# SpdReaderWriterSchematic.net
KiCad netlist of a schematic drawn in EAGLE
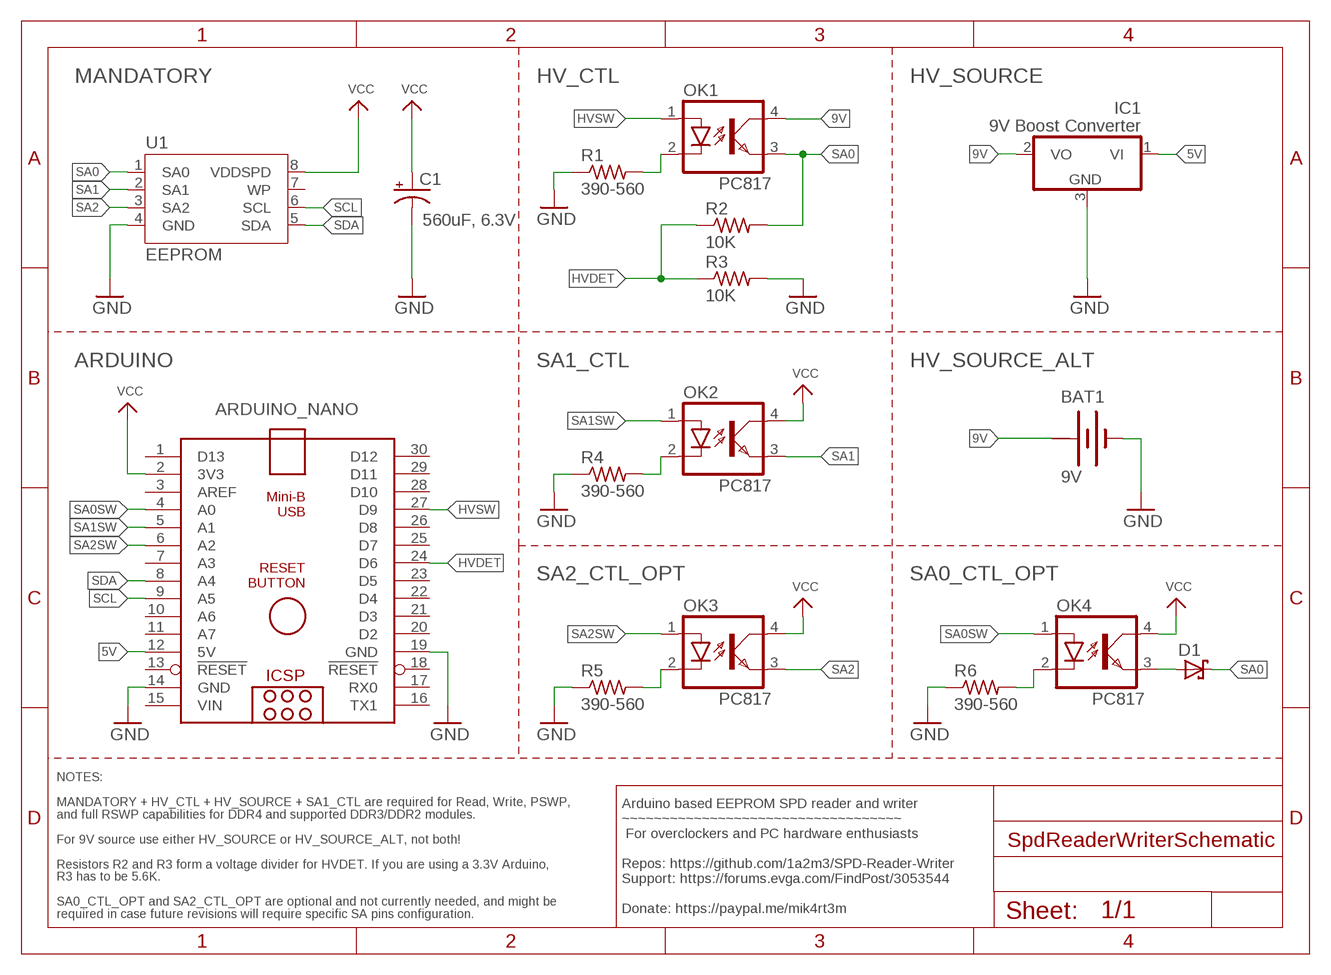
[diagram p0: schematic, sheet 1]

(export (version "E")
  (design (tool "Eeschema 10.0.6"))
  (components
    (comp (ref "ARDUINO_NANO")
      (value "ARDUINO_NANO")
      (footprint "eagle-import:ARDUINO_NANO")
      (libsource (lib "eagle-import") (part "ARDUINO_NANO"))
    )
    (comp (ref "BAT1")
      (value "9V")
      (footprint "eagle-import:BATTERY")
      (libsource (lib "eagle-import") (part "BATTERY"))
    )
    (comp (ref "C1")
      (value "560uF, 6.3V")
      (footprint "eagle-import:E5-8,5")
      (libsource (lib "eagle-import") (part "CPOL-USE5-8.5"))
    )
    (comp (ref "D1")
      (value "SCHOTTKY-DIODEDO35-7")
      (footprint "eagle-import:DO35-7")
      (libsource (lib "eagle-import") (part "SCHOTTKY-DIODEDO35-7"))
    )
    (comp (ref "IC1")
      (value "9V Boost Converter")
      (footprint "eagle-import:TO39")
      (libsource (lib "eagle-import") (part "78H24"))
    )
    (comp (ref "OK1")
      (value "PC817")
      (footprint "eagle-import:DIL04")
      (libsource (lib "eagle-import") (part "LTV816"))
    )
    (comp (ref "OK2")
      (value "PC817")
      (footprint "eagle-import:DIL04")
      (libsource (lib "eagle-import") (part "LTV816"))
    )
    (comp (ref "OK3")
      (value "PC817")
      (footprint "eagle-import:DIL04")
      (libsource (lib "eagle-import") (part "LTV816"))
    )
    (comp (ref "OK4")
      (value "PC817")
      (footprint "eagle-import:DIL04")
      (libsource (lib "eagle-import") (part "LTV816"))
    )
    (comp (ref "R1")
      (value "390-560")
      (footprint "eagle-import:0204_7")
      (libsource (lib "eagle-import") (part "rcl_334_R-US_0204/7"))
    )
    (comp (ref "R2")
      (value "10K")
      (footprint "eagle-import:0204_7")
      (libsource (lib "eagle-import") (part "R-US_0204/7"))
    )
    (comp (ref "R3")
      (value "10K")
      (footprint "eagle-import:0204_7")
      (libsource (lib "eagle-import") (part "R-US_0204/7"))
    )
    (comp (ref "R4")
      (value "390-560")
      (footprint "eagle-import:0204_7")
      (libsource (lib "eagle-import") (part "rcl_334_R-US_0204/7"))
    )
    (comp (ref "R5")
      (value "390-560")
      (footprint "eagle-import:0204_7")
      (libsource (lib "eagle-import") (part "rcl_334_R-US_0204/7"))
    )
    (comp (ref "R6")
      (value "390-560")
      (footprint "eagle-import:0204_7")
      (libsource (lib "eagle-import") (part "rcl_334_R-US_0204/7"))
    )
    (comp (ref "U1")
      (value "EEPROM")
      (footprint "eagle-import:2X04")
      (libsource (lib "eagle-import") (part "EEPROM"))
    )
  )
  (nets
    (net (code "1") (name "/+") (class "Default")
      (node (ref "BAT1") (pin "+@1") (pinfunction "+_+@1") (pintype "power_in"))
    )
    (net (code "2") (name "/VIN") (class "Default")
      (node (ref "ARDUINO_NANO") (pin "15") (pinfunction "VIN_15") (pintype "power_in"))
    )
    (net (code "3") (name "5V") (class "Default")
      (node (ref "ARDUINO_NANO") (pin "12") (pinfunction "5V_12") (pintype "power_in"))
      (node (ref "IC1") (pin "1") (pinfunction "VI_1") (pintype "input"))
    )
    (net (code "4") (name "9V") (class "Default")
      (node (ref "BAT1") (pin "+") (pinfunction "+_+") (pintype "power_in"))
      (node (ref "IC1") (pin "2") (pinfunction "VO_2") (pintype "passive"))
      (node (ref "OK1") (pin "4") (pinfunction "COL_4") (pintype "passive"))
    )
    (net (code "5") (name "GND") (class "Default")
      (node (ref "ARDUINO_NANO") (pin "14") (pinfunction "GND_14") (pintype "power_in"))
      (node (ref "ARDUINO_NANO") (pin "19") (pinfunction "GND_19") (pintype "power_in"))
      (node (ref "BAT1") (pin "-") (pinfunction "-_-") (pintype "power_in"))
      (node (ref "C1") (pin "-") (pinfunction "-_-") (pintype "passive"))
      (node (ref "IC1") (pin "3") (pinfunction "GND_3") (pintype "passive"))
      (node (ref "R1") (pin "1") (pinfunction "1_1") (pintype "passive"))
      (node (ref "R3") (pin "2") (pinfunction "2_2") (pintype "passive"))
      (node (ref "R4") (pin "1") (pinfunction "1_1") (pintype "passive"))
      (node (ref "R5") (pin "1") (pinfunction "1_1") (pintype "passive"))
      (node (ref "R6") (pin "1") (pinfunction "1_1") (pintype "passive"))
      (node (ref "U1") (pin "4") (pinfunction "GND_4") (pintype "power_in"))
    )
    (net (code "6") (name "HVDET") (class "Default")
      (node (ref "ARDUINO_NANO") (pin "24") (pinfunction "D6_24") (pintype "bidirectional"))
      (node (ref "R2") (pin "1") (pinfunction "1_1") (pintype "passive"))
      (node (ref "R3") (pin "1") (pinfunction "1_1") (pintype "passive"))
    )
    (net (code "7") (name "HVSW") (class "Default")
      (node (ref "ARDUINO_NANO") (pin "27") (pinfunction "D9_27") (pintype "bidirectional"))
      (node (ref "OK1") (pin "1") (pinfunction "A_1") (pintype "passive"))
    )
    (net (code "8") (name "Net-(OK1-C)") (class "Default")
      (node (ref "OK1") (pin "2") (pinfunction "C_2") (pintype "passive"))
      (node (ref "R1") (pin "2") (pinfunction "2_2") (pintype "passive"))
    )
    (net (code "9") (name "Net-(OK2-C)") (class "Default")
      (node (ref "OK2") (pin "2") (pinfunction "C_2") (pintype "passive"))
      (node (ref "R4") (pin "2") (pinfunction "2_2") (pintype "passive"))
    )
    (net (code "10") (name "Net-(OK3-C)") (class "Default")
      (node (ref "OK3") (pin "2") (pinfunction "C_2") (pintype "passive"))
      (node (ref "R5") (pin "2") (pinfunction "2_2") (pintype "passive"))
    )
    (net (code "11") (name "Net-(OK4-C)") (class "Default")
      (node (ref "OK4") (pin "2") (pinfunction "C_2") (pintype "passive"))
      (node (ref "R6") (pin "2") (pinfunction "2_2") (pintype "passive"))
    )
    (net (code "12") (name "Net-(OK4-EMIT)") (class "Default")
      (node (ref "D1") (pin "A") (pinfunction "A_A") (pintype "passive"))
      (node (ref "OK4") (pin "3") (pinfunction "EMIT_3") (pintype "passive"))
    )
    (net (code "13") (name "SA0") (class "Default")
      (node (ref "D1") (pin "C") (pinfunction "C_C") (pintype "passive"))
      (node (ref "OK1") (pin "3") (pinfunction "EMIT_3") (pintype "passive"))
      (node (ref "R2") (pin "2") (pinfunction "2_2") (pintype "passive"))
      (node (ref "U1") (pin "1") (pinfunction "SA0_1") (pintype "input"))
    )
    (net (code "14") (name "SA0SW") (class "Default")
      (node (ref "ARDUINO_NANO") (pin "4") (pinfunction "A0_4") (pintype "bidirectional"))
      (node (ref "OK4") (pin "1") (pinfunction "A_1") (pintype "passive"))
    )
    (net (code "15") (name "SA1") (class "Default")
      (node (ref "OK2") (pin "3") (pinfunction "EMIT_3") (pintype "passive"))
      (node (ref "U1") (pin "2") (pinfunction "SA1_2") (pintype "input"))
    )
    (net (code "16") (name "SA1SW") (class "Default")
      (node (ref "ARDUINO_NANO") (pin "5") (pinfunction "A1_5") (pintype "bidirectional"))
      (node (ref "OK2") (pin "1") (pinfunction "A_1") (pintype "passive"))
    )
    (net (code "17") (name "SA2") (class "Default")
      (node (ref "OK3") (pin "3") (pinfunction "EMIT_3") (pintype "passive"))
      (node (ref "U1") (pin "3") (pinfunction "SA2_3") (pintype "input"))
    )
    (net (code "18") (name "SA2SW") (class "Default")
      (node (ref "ARDUINO_NANO") (pin "6") (pinfunction "A2_6") (pintype "bidirectional"))
      (node (ref "OK3") (pin "1") (pinfunction "A_1") (pintype "passive"))
    )
    (net (code "19") (name "SCL") (class "Default")
      (node (ref "ARDUINO_NANO") (pin "9") (pinfunction "A5_9") (pintype "bidirectional"))
      (node (ref "U1") (pin "6") (pinfunction "SCL_6") (pintype "input"))
    )
    (net (code "20") (name "SDA") (class "Default")
      (node (ref "ARDUINO_NANO") (pin "8") (pinfunction "A4_8") (pintype "bidirectional"))
      (node (ref "U1") (pin "5") (pinfunction "SDA_5") (pintype "bidirectional"))
    )
    (net (code "21") (name "VCC") (class "Default")
      (node (ref "ARDUINO_NANO") (pin "2") (pinfunction "3V3_2") (pintype "output"))
      (node (ref "C1") (pin "+") (pinfunction "+_+") (pintype "passive"))
      (node (ref "OK2") (pin "4") (pinfunction "COL_4") (pintype "passive"))
      (node (ref "OK3") (pin "4") (pinfunction "COL_4") (pintype "passive"))
      (node (ref "OK4") (pin "4") (pinfunction "COL_4") (pintype "passive"))
      (node (ref "U1") (pin "8") (pinfunction "VDDSPD_8") (pintype "power_in"))
    )
    (net (code "22") (name "unconnected-(ARDUINO_NANO-A3-Pad7)") (class "Default")
      (node (ref "ARDUINO_NANO") (pin "7") (pinfunction "A3_7") (pintype "bidirectional"))
    )
    (net (code "23") (name "unconnected-(ARDUINO_NANO-A6-Pad10)") (class "Default")
      (node (ref "ARDUINO_NANO") (pin "10") (pinfunction "A6_10") (pintype "bidirectional"))
    )
    (net (code "24") (name "unconnected-(ARDUINO_NANO-A7-Pad11)") (class "Default")
      (node (ref "ARDUINO_NANO") (pin "11") (pinfunction "A7_11") (pintype "bidirectional"))
    )
    (net (code "25") (name "unconnected-(ARDUINO_NANO-AREF-Pad3)") (class "Default")
      (node (ref "ARDUINO_NANO") (pin "3") (pinfunction "AREF_3") (pintype "input"))
    )
    (net (code "26") (name "unconnected-(ARDUINO_NANO-D2-Pad20)") (class "Default")
      (node (ref "ARDUINO_NANO") (pin "20") (pinfunction "D2_20") (pintype "bidirectional"))
    )
    (net (code "27") (name "unconnected-(ARDUINO_NANO-D3-Pad21)") (class "Default")
      (node (ref "ARDUINO_NANO") (pin "21") (pinfunction "D3_21") (pintype "bidirectional"))
    )
    (net (code "28") (name "unconnected-(ARDUINO_NANO-D4-Pad22)") (class "Default")
      (node (ref "ARDUINO_NANO") (pin "22") (pinfunction "D4_22") (pintype "bidirectional"))
    )
    (net (code "29") (name "unconnected-(ARDUINO_NANO-D5-Pad23)") (class "Default")
      (node (ref "ARDUINO_NANO") (pin "23") (pinfunction "D5_23") (pintype "bidirectional"))
    )
    (net (code "30") (name "unconnected-(ARDUINO_NANO-D7-Pad25)") (class "Default")
      (node (ref "ARDUINO_NANO") (pin "25") (pinfunction "D7_25") (pintype "bidirectional"))
    )
    (net (code "31") (name "unconnected-(ARDUINO_NANO-D8-Pad26)") (class "Default")
      (node (ref "ARDUINO_NANO") (pin "26") (pinfunction "D8_26") (pintype "bidirectional"))
    )
    (net (code "32") (name "unconnected-(ARDUINO_NANO-D10-Pad28)") (class "Default")
      (node (ref "ARDUINO_NANO") (pin "28") (pinfunction "D10_28") (pintype "bidirectional"))
    )
    (net (code "33") (name "unconnected-(ARDUINO_NANO-D11-Pad29)") (class "Default")
      (node (ref "ARDUINO_NANO") (pin "29") (pinfunction "D11_29") (pintype "bidirectional"))
    )
    (net (code "34") (name "unconnected-(ARDUINO_NANO-D12-Pad30)") (class "Default")
      (node (ref "ARDUINO_NANO") (pin "30") (pinfunction "D12_30") (pintype "bidirectional"))
    )
    (net (code "35") (name "unconnected-(ARDUINO_NANO-D13-Pad1)") (class "Default")
      (node (ref "ARDUINO_NANO") (pin "1") (pinfunction "D13_1") (pintype "bidirectional"))
    )
    (net (code "36") (name "unconnected-(ARDUINO_NANO-RX0-Pad17)") (class "Default")
      (node (ref "ARDUINO_NANO") (pin "17") (pinfunction "RX0_17") (pintype "bidirectional"))
    )
    (net (code "37") (name "unconnected-(ARDUINO_NANO-TX1-Pad16)") (class "Default")
      (node (ref "ARDUINO_NANO") (pin "16") (pinfunction "TX1_16") (pintype "bidirectional"))
    )
    (net (code "38") (name "unconnected-(ARDUINO_NANO-~{RESET}-Pad13)") (class "Default")
      (node (ref "ARDUINO_NANO") (pin "13") (pinfunction "~{RESET}_13") (pintype "input"))
    )
    (net (code "39") (name "unconnected-(ARDUINO_NANO-~{RESET}-Pad18)") (class "Default")
      (node (ref "ARDUINO_NANO") (pin "18") (pinfunction "~{RESET}_18") (pintype "input"))
    )
    (net (code "40") (name "unconnected-(U1-WP-Pad7)") (class "Default")
      (node (ref "U1") (pin "7") (pinfunction "WP_7") (pintype "output"))
    )
  )
)
